# FlightController.net
KiCad netlist of a schematic drawn in Altium Designer
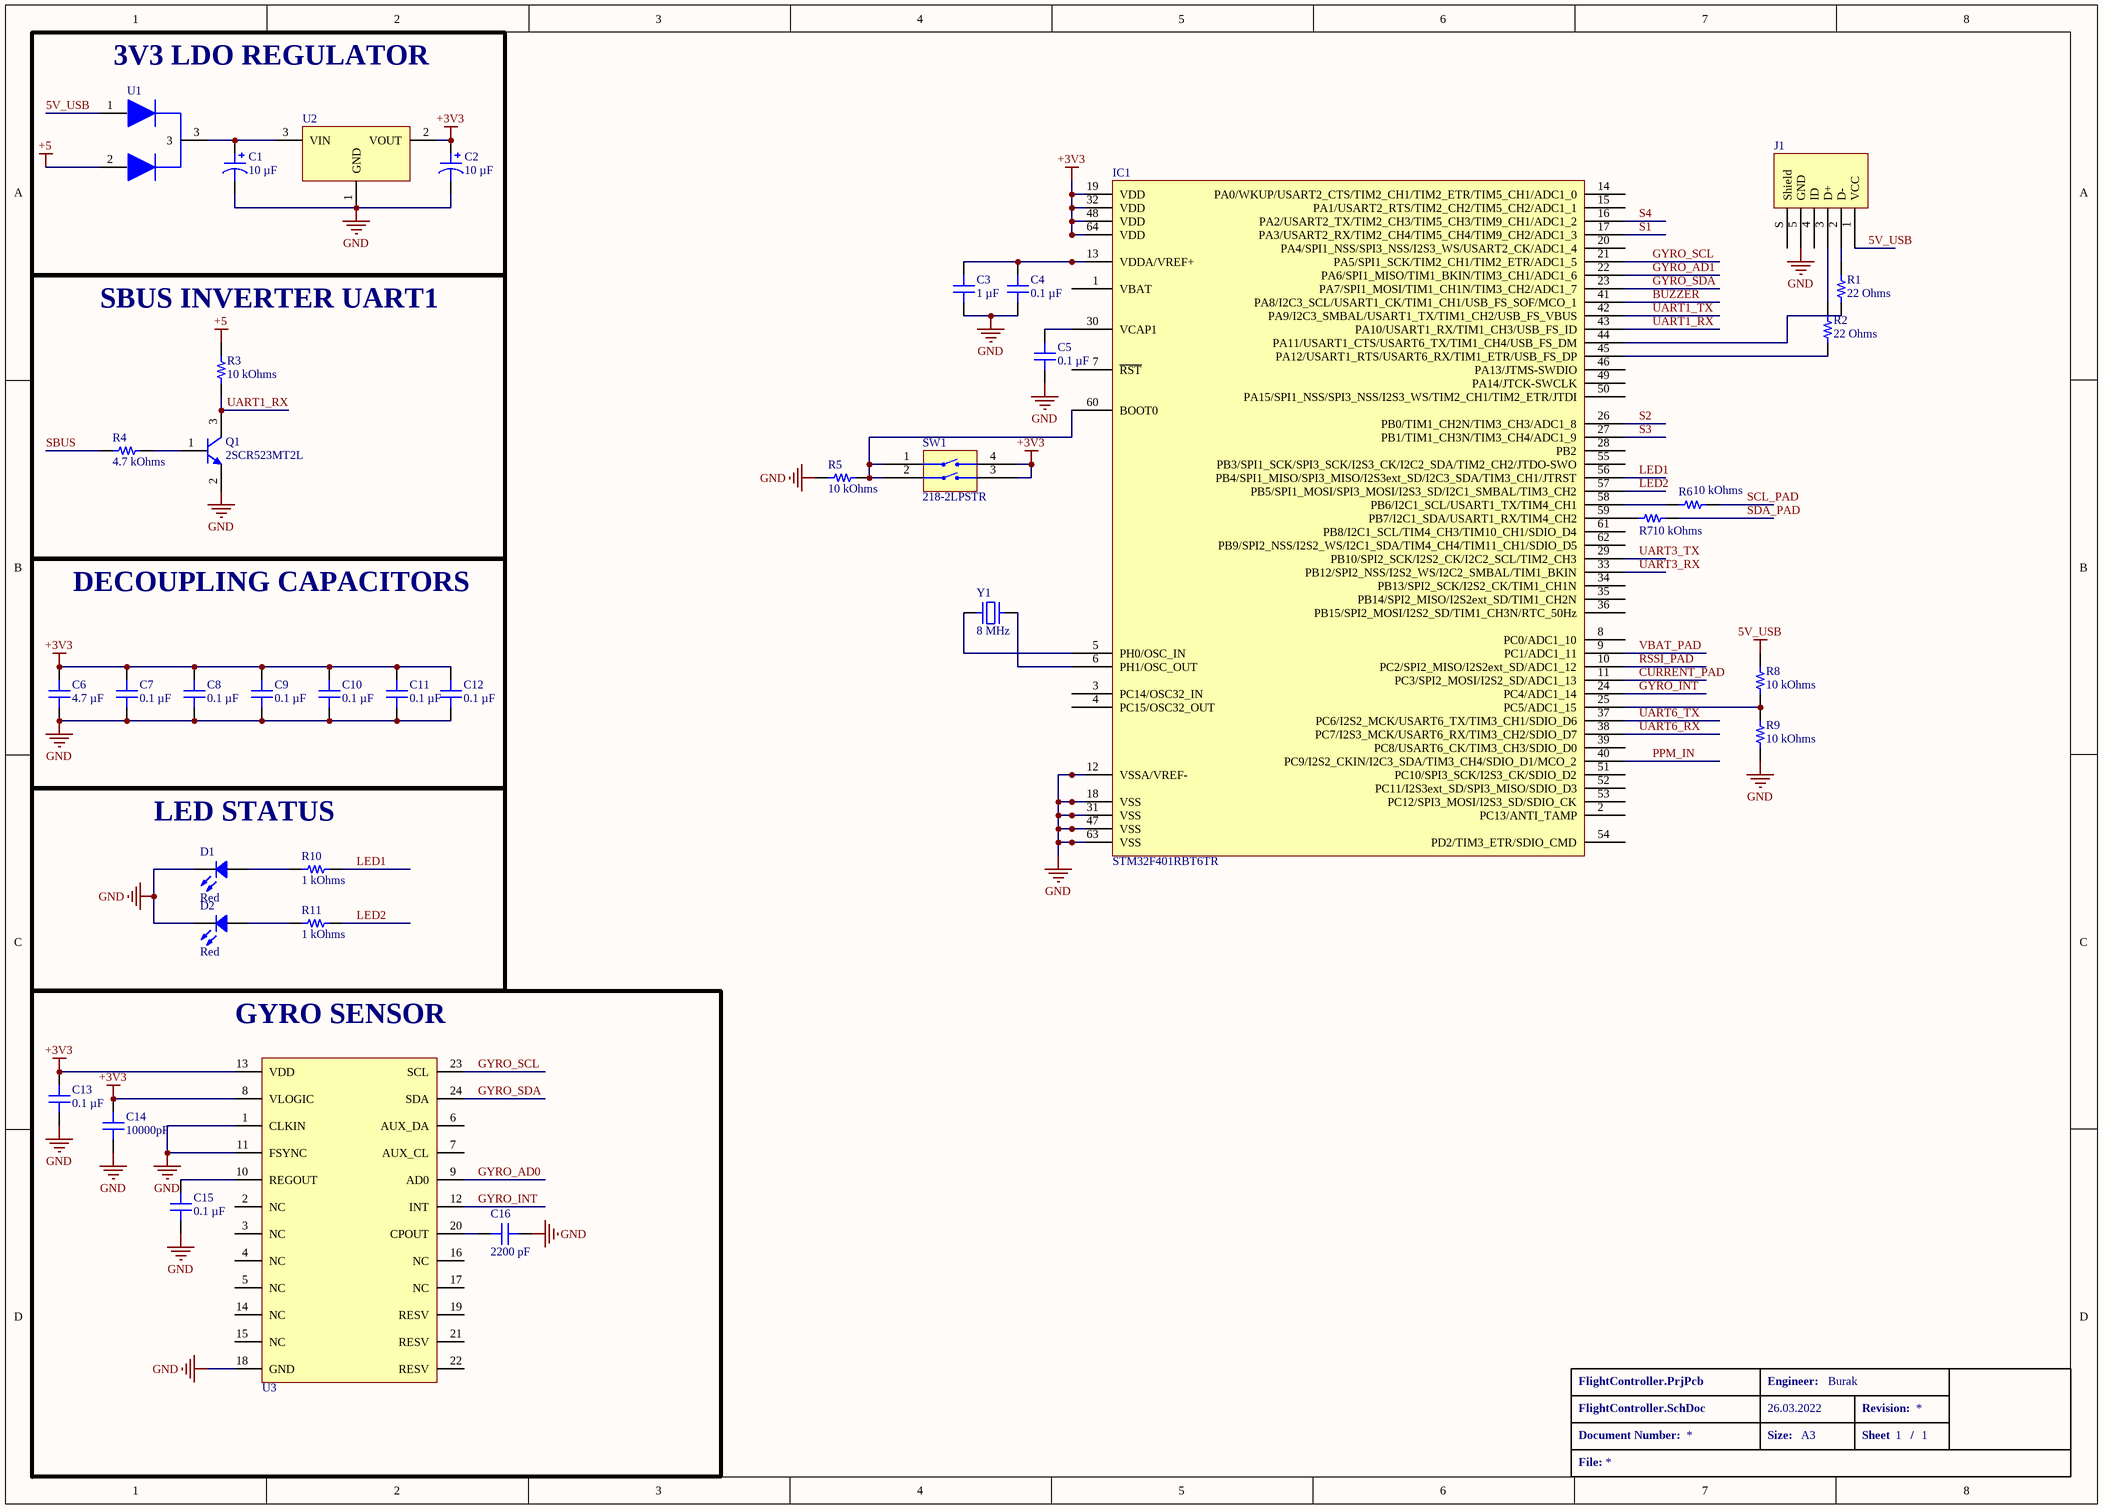
[diagram p0: FlightController.SchDoc]

(export (version "E")
  (design (tool "Eeschema 10.0.6"))
  (components
    (comp (ref "C1")
      (value "10 µF")
      (footprint "CAP ALSMD POLY 5.3MM H5.8MM")
      (description "CAP ALUM POLY 10UF 20% 16V SMD")
      (fields (field (name "PART NUMBER") "875105359001") (field (name "MANUFACTURER") "Würth Elektronik"))
      (libsource (lib "Celestial Altium Library - altium_library") (part "Polarised Capacitor"))
    )
    (comp (ref "C2")
      (value "10 µF")
      (footprint "CAP ALSMD POLY 5.3MM H5.8MM")
      (description "CAP ALUM POLY 10UF 20% 16V SMD")
      (fields (field (name "PART NUMBER") "875105359001") (field (name "MANUFACTURER") "Würth Elektronik"))
      (libsource (lib "Celestial Altium Library - altium_library") (part "Polarised Capacitor"))
    )
    (comp (ref "C3")
      (value "1 µF")
      (footprint "CAP 0805_2012")
      (description "CAP CER 1UF 16V X8R 0805")
      (fields
        (field (name "PART NUMBER") "C2012X8R1C105K125AB")
        (field (name "MANUFACTURER") "TDK Corporation")
      )
      (libsource (lib "Celestial Altium Library - altium_library") (part "Capacitor"))
    )
    (comp (ref "C4")
      (value "0.1 µF")
      (footprint "CAP 0805_2012")
      (description "CAP CER 0.1UF 16V X7R 0805")
      (fields
        (field (name "PART NUMBER") "160R15W104KV4T")
        (field (name "MANUFACTURER") "Johanson Dielectrics Inc.")
      )
      (libsource (lib "Celestial Altium Library - altium_library") (part "Capacitor"))
    )
    (comp (ref "C5")
      (value "0.1 µF")
      (footprint "CAP 0805_2012")
      (description "CAP CER 0.1UF 16V X7R 0805")
      (fields
        (field (name "PART NUMBER") "160R15W104KV4T")
        (field (name "MANUFACTURER") "Johanson Dielectrics Inc.")
      )
      (libsource (lib "Celestial Altium Library - altium_library") (part "Capacitor"))
    )
    (comp (ref "C6")
      (value "4.7 µF")
      (footprint "CAP 0805_2012")
      (description "CAP CER 4.7UF 10V X5R 0805")
      (fields
        (field (name "PART NUMBER") "CL21A475KPFNNNE")
        (field (name "MANUFACTURER") "Samsung Electro-Mechanics")
      )
      (libsource (lib "Celestial Altium Library - altium_library") (part "Capacitor"))
    )
    (comp (ref "C7")
      (value "0.1 µF")
      (footprint "CAP 0805_2012")
      (description "CAP CER 0.1UF 16V X7R 0805")
      (fields
        (field (name "PART NUMBER") "160R15W104KV4T")
        (field (name "MANUFACTURER") "Johanson Dielectrics Inc.")
      )
      (libsource (lib "Celestial Altium Library - altium_library") (part "Capacitor"))
    )
    (comp (ref "C8")
      (value "0.1 µF")
      (footprint "CAP 0805_2012")
      (description "CAP CER 0.1UF 16V X7R 0805")
      (fields
        (field (name "PART NUMBER") "160R15W104KV4T")
        (field (name "MANUFACTURER") "Johanson Dielectrics Inc.")
      )
      (libsource (lib "Celestial Altium Library - altium_library") (part "Capacitor"))
    )
    (comp (ref "C9")
      (value "0.1 µF")
      (footprint "CAP 0805_2012")
      (description "CAP CER 0.1UF 16V X7R 0805")
      (fields
        (field (name "PART NUMBER") "160R15W104KV4T")
        (field (name "MANUFACTURER") "Johanson Dielectrics Inc.")
      )
      (libsource (lib "Celestial Altium Library - altium_library") (part "Capacitor"))
    )
    (comp (ref "C10")
      (value "0.1 µF")
      (footprint "CAP 0805_2012")
      (description "CAP CER 0.1UF 16V X7R 0805")
      (fields
        (field (name "PART NUMBER") "160R15W104KV4T")
        (field (name "MANUFACTURER") "Johanson Dielectrics Inc.")
      )
      (libsource (lib "Celestial Altium Library - altium_library") (part "Capacitor"))
    )
    (comp (ref "C11")
      (value "0.1 µF")
      (footprint "CAP 0805_2012")
      (description "CAP CER 0.1UF 16V X7R 0805")
      (fields
        (field (name "PART NUMBER") "160R15W104KV4T")
        (field (name "MANUFACTURER") "Johanson Dielectrics Inc.")
      )
      (libsource (lib "Celestial Altium Library - altium_library") (part "Capacitor"))
    )
    (comp (ref "C12")
      (value "0.1 µF")
      (footprint "CAP 0805_2012")
      (description "CAP CER 0.1UF 16V X7R 0805")
      (fields
        (field (name "PART NUMBER") "160R15W104KV4T")
        (field (name "MANUFACTURER") "Johanson Dielectrics Inc.")
      )
      (libsource (lib "Celestial Altium Library - altium_library") (part "Capacitor"))
    )
    (comp (ref "C13")
      (value "0.1 µF")
      (footprint "CAP 0805_2012")
      (description "CAP CER 0.1UF 16V X7R 0805")
      (fields
        (field (name "PART NUMBER") "0805B104K160CT")
        (field (name "MANUFACTURER") "Walsin Technology Corporation")
      )
      (libsource (lib "Celestial Altium Library - altium_library") (part "Capacitor"))
    )
    (comp (ref "C14")
      (value "10000pF")
      (footprint "CAP 0805_2012")
      (description "CAP CER 10000PF 16V X7R 0805")
      (fields (field (name "PART NUMBER") "0805YC103KAT2A") (field (name "MANUFACTURER") "AVX Corporation"))
      (libsource (lib "Celestial Altium Library - altium_library") (part "Capacitor"))
    )
    (comp (ref "C15")
      (value "0.1 µF")
      (footprint "CAP 0805_2012")
      (description "CAP CER 0.1UF 16V X7R 0805")
      (fields
        (field (name "PART NUMBER") "0805B104K160CT")
        (field (name "MANUFACTURER") "Walsin Technology Corporation")
      )
      (libsource (lib "Celestial Altium Library - altium_library") (part "Capacitor"))
    )
    (comp (ref "C16")
      (value "2200 pF")
      (footprint "CAP 0805_2012")
      (description "CAP CER 2200PF 10V X7R 0805")
      (fields (field (name "PART NUMBER") "885012207009") (field (name "MANUFACTURER") "Würth Elektronik"))
      (libsource (lib "Celestial Altium Library - altium_library") (part "Capacitor"))
    )
    (comp (ref "D1")
      (value "Red")
      (footprint "LED 1206_3216 RED")
      (description "LED RED CLEAR 1206 SMD")
      (fields (field (name "PART NUMBER") "5973111402F") (field (name "MANUFACTURER") "Dialight"))
      (libsource (lib "Celestial Altium Library - altium_library") (part "LED"))
    )
    (comp (ref "D2")
      (value "Red")
      (footprint "LED 1206_3216 RED")
      (description "LED RED CLEAR 1206 SMD")
      (fields (field (name "PART NUMBER") "5973111402F") (field (name "MANUFACTURER") "Dialight"))
      (libsource (lib "Celestial Altium Library - altium_library") (part "LED"))
    )
    (comp (ref "IC1")
      (value "STM32F401RBT6TR")
      (footprint "ST LQFP-64 10X10MM")
      (description "IC MCU 32BIT 128KB FLASH 64LQFP")
      (fields (field (name "MANUFACTURER") "STMicroelectronics"))
      (libsource (lib "Celestial Altium Library - altium_library") (part "ST STM32F401 64PIN"))
    )
    (comp (ref "J1")
      (value "10118193-0001LF")
      (footprint "FCI USB 10118193-0001LF")
      (description "CONN RCPT USB2.0 MICRO B SMD R/A")
      (fields (field (name "MANUFACTURER") "Amphenol ICC (FCI)"))
      (libsource (lib "Celestial Altium Library - altium_library") (part "USB 2.0 Type B Micro"))
    )
    (comp (ref "Q1")
      (value "2SCR523MT2L")
      (footprint "ROHM SOT-723")
      (description "TRANS NPN 50V 0.1A VMT3")
      (fields (field (name "MANUFACTURER") "Rohm Semiconductor"))
      (libsource (lib "Celestial Altium Library - altium_library") (part "ROHM NPN SOT723 BEC"))
    )
    (comp (ref "R1")
      (value "22 Ohms")
      (footprint "RES 0805_2012")
      (description "RES SMD 22 OHM 0.1% 1/10W 0805")
      (fields
        (field (name "PART NUMBER") "CPF0805B22RE1")
        (field (name "MANUFACTURER") "TE Connectivity Passive Product")
      )
      (libsource (lib "Celestial Altium Library - altium_library") (part "Resistor"))
    )
    (comp (ref "R2")
      (value "22 Ohms")
      (footprint "RES 0805_2012")
      (description "RES SMD 22 OHM 0.1% 1/10W 0805")
      (fields
        (field (name "PART NUMBER") "CPF0805B22RE1")
        (field (name "MANUFACTURER") "TE Connectivity Passive Product")
      )
      (libsource (lib "Celestial Altium Library - altium_library") (part "Resistor"))
    )
    (comp (ref "R3")
      (value "10 kOhms")
      (footprint "RES 0805_2012")
      (description "RES 10K OHM 0.1% 1/10W 0805")
      (fields
        (field (name "PART NUMBER") "RNCS0805BKE10K0")
        (field (name "MANUFACTURER") "Stackpole Electronics Inc")
      )
      (libsource (lib "Celestial Altium Library - altium_library") (part "Resistor"))
    )
    (comp (ref "R4")
      (value "4.7 kOhms")
      (footprint "RES 0805_2012")
      (description "RES SMD 4.7K OHM 5% 0.4W 0805")
      (fields (field (name "PART NUMBER") "RCS08054K70JNEA") (field (name "MANUFACTURER") "Vishay Dale"))
      (libsource (lib "Celestial Altium Library - altium_library") (part "Resistor"))
    )
    (comp (ref "R5")
      (value "10 kOhms")
      (footprint "RES 0805_2012")
      (description "RES 10K OHM 0.1% 1/10W 0805")
      (fields
        (field (name "PART NUMBER") "RNCS0805BKE10K0")
        (field (name "MANUFACTURER") "Stackpole Electronics Inc")
      )
      (libsource (lib "Celestial Altium Library - altium_library") (part "Resistor"))
    )
    (comp (ref "R6")
      (value "10 kOhms")
      (footprint "RES 0805_2012")
      (description "RES 10K OHM 0.1% 1/10W 0805")
      (fields
        (field (name "PART NUMBER") "RNCS0805BKE10K0")
        (field (name "MANUFACTURER") "Stackpole Electronics Inc")
      )
      (libsource (lib "Celestial Altium Library - altium_library") (part "Resistor"))
    )
    (comp (ref "R7")
      (value "10 kOhms")
      (footprint "RES 0805_2012")
      (description "RES 10K OHM 0.1% 1/10W 0805")
      (fields
        (field (name "PART NUMBER") "RNCS0805BKE10K0")
        (field (name "MANUFACTURER") "Stackpole Electronics Inc")
      )
      (libsource (lib "Celestial Altium Library - altium_library") (part "Resistor"))
    )
    (comp (ref "R8")
      (value "10 kOhms")
      (footprint "RES 0805_2012")
      (description "RES 10K OHM 0.1% 1/10W 0805")
      (fields
        (field (name "PART NUMBER") "RNCS0805BKE10K0")
        (field (name "MANUFACTURER") "Stackpole Electronics Inc")
      )
      (libsource (lib "Celestial Altium Library - altium_library") (part "Resistor"))
    )
    (comp (ref "R9")
      (value "10 kOhms")
      (footprint "RES 0805_2012")
      (description "RES 10K OHM 0.1% 1/10W 0805")
      (fields
        (field (name "PART NUMBER") "RNCS0805BKE10K0")
        (field (name "MANUFACTURER") "Stackpole Electronics Inc")
      )
      (libsource (lib "Celestial Altium Library - altium_library") (part "Resistor"))
    )
    (comp (ref "R10")
      (value "1 kOhms")
      (footprint "RES 0805_2012")
      (description "RES 1K OHM 0.1% 1/10W 0805")
      (fields
        (field (name "PART NUMBER") "RNCS0805BKE1K00")
        (field (name "MANUFACTURER") "Stackpole Electronics Inc")
      )
      (libsource (lib "Celestial Altium Library - altium_library") (part "Resistor"))
    )
    (comp (ref "R11")
      (value "1 kOhms")
      (footprint "RES 0805_2012")
      (description "RES 1K OHM 0.1% 1/10W 0805")
      (fields
        (field (name "PART NUMBER") "RNCS0805BKE1K00")
        (field (name "MANUFACTURER") "Stackpole Electronics Inc")
      )
      (libsource (lib "Celestial Altium Library - altium_library") (part "Resistor"))
    )
    (comp (ref "SW1")
      (value "218-2LPSTR")
      (footprint "CTS 218-2LPJ")
      (description "SWITCH SLIDE DIP SPST 25MA 24V")
      (fields (field (name "MANUFACTURER") "CTS Electrocomponents"))
      (libsource (lib "Celestial Altium Library - altium_library") (part "DIP SW 2P"))
    )
    (comp (ref "U1")
      (value "BAT54C")
      (footprint "SOT-23")
      (description "Rectifier Diode Small Signal Schottky 30V 0.2A 5ns Automotive 3-Pin SOT-23 T/R")
      (fields
        (field (name "MANUFACTURER") "NXP Semiconductors")
        (field (name "VOLTAGE") "30V")
        (field (name "DESIGNED BY") "Burak")
      )
      (libsource (lib "UDEMY_Library") (part "BAT54C"))
    )
    (comp (ref "U2")
      (value "IC REG LDO 3.3V 1A SOT223")
      (footprint "SOT223")
      (fields
        (field (name "MANUFACTURER") "ON Semiconductor")
        (field (name "MANUFACTURER PART NUMBER") "NCP1117ST33T3G")
        (field (name "DESIGNED BY") "Burak")
      )
      (libsource (lib "UDEMY_Library") (part "NCP1117ST33T3G"))
    )
    (comp (ref "U3")
      (value "GYRO SENSOR")
      (footprint "QFN_24PINS")
      (description "IMU ACCEL/GYRO 3-AXIS I2C 24QFN")
      (fields
        (field (name "MANUFACTURER") "TDK InvenSense")
        (field (name "MANUFACTURER PART NUMBER") "MPU-6050")
        (field (name "DESIGNED BY") "Burak")
      )
      (libsource (lib "UDEMY_Library") (part "MPU-6050"))
    )
    (comp (ref "Y1")
      (value "8 MHz")
      (footprint "ABRACON ABLS")
      (description "CRYSTAL 8.0000MHZ 18PF SMD")
      (fields (field (name "PART NUMBER") "ABLS-8.000MHZ-SD7Y-T") (field (name "MANUFACTURER") "Abracon LLC"))
      (libsource (lib "Celestial Altium Library - altium_library") (part "Abracon Crystal ABLS"))
    )
  )
  (nets
    (net (code "1") (name "+3V3") (class "Default")
      (node (ref "C10") (pin "2") (pinfunction "2_2") (pintype "passive"))
      (node (ref "C11") (pin "2") (pinfunction "2_2") (pintype "passive"))
      (node (ref "C12") (pin "2") (pinfunction "2_2") (pintype "passive"))
      (node (ref "C13") (pin "2") (pinfunction "2_2") (pintype "passive"))
      (node (ref "C14") (pin "2") (pinfunction "2_2") (pintype "passive"))
      (node (ref "C2") (pin "1") (pinfunction "1_1") (pintype "passive"))
      (node (ref "C6") (pin "2") (pinfunction "2_2") (pintype "passive"))
      (node (ref "C7") (pin "2") (pinfunction "2_2") (pintype "passive"))
      (node (ref "C8") (pin "2") (pinfunction "2_2") (pintype "passive"))
      (node (ref "C9") (pin "2") (pinfunction "2_2") (pintype "passive"))
      (node (ref "IC1") (pin "19") (pinfunction "VDD_19") (pintype "passive"))
      (node (ref "IC1") (pin "32") (pinfunction "VDD_32") (pintype "passive"))
      (node (ref "IC1") (pin "48") (pinfunction "VDD_48") (pintype "passive"))
      (node (ref "IC1") (pin "64") (pinfunction "VDD_64") (pintype "passive"))
      (node (ref "SW1") (pin "3") (pinfunction "GND_3") (pintype "passive"))
      (node (ref "SW1") (pin "4") (pinfunction "GND_4") (pintype "passive"))
      (node (ref "U2") (pin "2") (pinfunction "VOUT_2") (pintype "passive"))
      (node (ref "U3") (pin "13") (pinfunction "VDD_13") (pintype "passive"))
      (node (ref "U3") (pin "8") (pinfunction "VLOGIC_8") (pintype "passive"))
    )
    (net (code "2") (name "+5") (class "Default")
      (node (ref "R3") (pin "2") (pinfunction "2_2") (pintype "passive"))
      (node (ref "U1") (pin "2") (pinfunction "2_2") (pintype "passive"))
    )
    (net (code "3") (name "/BUZZER") (class "Default")
      (node (ref "IC1") (pin "41") (pinfunction "PA8/I2C3_SCL/USART1_CK/TIM1_CH1/USB_FS_SOF/MCO_1_41") (pintype "passive"))
    )
    (net (code "4") (name "/CURRENT_PAD") (class "Default")
      (node (ref "IC1") (pin "11") (pinfunction "PC3/SPI2_MOSI/I2S2_SD/ADC1_13_11") (pintype "passive"))
    )
    (net (code "5") (name "/GYRO_AD0") (class "Default")
      (node (ref "U3") (pin "9") (pinfunction "AD0_9") (pintype "passive"))
    )
    (net (code "6") (name "/GYRO_AD1") (class "Default")
      (node (ref "IC1") (pin "22") (pinfunction "PA6/SPI1_MISO/TIM1_BKIN/TIM3_CH1/ADC1_6_22") (pintype "passive"))
    )
    (net (code "7") (name "/GYRO_INT") (class "Default")
      (node (ref "IC1") (pin "24") (pinfunction "PC4/ADC1_14_24") (pintype "passive"))
      (node (ref "U3") (pin "12") (pinfunction "INT_12") (pintype "passive"))
    )
    (net (code "8") (name "/GYRO_SCL") (class "Default")
      (node (ref "IC1") (pin "21") (pinfunction "PA5/SPI1_SCK/TIM2_CH1/TIM2_ETR/ADC1_5_21") (pintype "passive"))
      (node (ref "U3") (pin "23") (pinfunction "SCL_23") (pintype "passive"))
    )
    (net (code "9") (name "/GYRO_SDA") (class "Default")
      (node (ref "IC1") (pin "23") (pinfunction "PA7/SPI1_MOSI/TIM1_CH1N/TIM3_CH2/ADC1_7_23") (pintype "passive"))
      (node (ref "U3") (pin "24") (pinfunction "SDA_24") (pintype "passive"))
    )
    (net (code "10") (name "/LED1") (class "Default")
      (node (ref "IC1") (pin "56") (pinfunction "PB4/SPI1_MISO/SPI3_MISO/I2S3ext_SD/I2C3_SDA/TIM3_CH1/JTRST_56") (pintype "passive"))
      (node (ref "R10") (pin "2") (pinfunction "2_2") (pintype "passive"))
    )
    (net (code "11") (name "/LED2") (class "Default")
      (node (ref "IC1") (pin "57") (pinfunction "PB5/SPI1_MOSI/SPI3_MOSI/I2S3_SD/I2C1_SMBAL/TIM3_CH2_57") (pintype "passive"))
      (node (ref "R11") (pin "2") (pinfunction "2_2") (pintype "passive"))
    )
    (net (code "12") (name "/PPM_IN") (class "Default")
      (node (ref "IC1") (pin "40") (pinfunction "PC9/I2S2_CKIN/I2C3_SDA/TIM3_CH4/SDIO_D1/MCO_2_40") (pintype "passive"))
    )
    (net (code "13") (name "/RSSI_PAD") (class "Default")
      (node (ref "IC1") (pin "10") (pinfunction "PC2/SPI2_MISO/I2S2ext_SD/ADC1_12_10") (pintype "passive"))
    )
    (net (code "14") (name "/S1") (class "Default")
      (node (ref "IC1") (pin "17") (pinfunction "PA3/USART2_RX/TIM2_CH4/TIM5_CH4/TIM9_CH2/ADC1_3_17") (pintype "passive"))
    )
    (net (code "15") (name "/S2") (class "Default")
      (node (ref "IC1") (pin "26") (pinfunction "PB0/TIM1_CH2N/TIM3_CH3/ADC1_8_26") (pintype "passive"))
    )
    (net (code "16") (name "/S3") (class "Default")
      (node (ref "IC1") (pin "27") (pinfunction "PB1/TIM1_CH3N/TIM3_CH4/ADC1_9_27") (pintype "passive"))
    )
    (net (code "17") (name "/S4") (class "Default")
      (node (ref "IC1") (pin "16") (pinfunction "PA2/USART2_TX/TIM2_CH3/TIM5_CH3/TIM9_CH1/ADC1_2_16") (pintype "passive"))
    )
    (net (code "18") (name "/SBUS") (class "Default")
      (node (ref "R4") (pin "1") (pinfunction "1_1") (pintype "passive"))
    )
    (net (code "19") (name "/SCL_PAD") (class "Default")
      (node (ref "R6") (pin "1") (pinfunction "1_1") (pintype "passive"))
    )
    (net (code "20") (name "/SDA_PAD") (class "Default")
      (node (ref "R7") (pin "1") (pinfunction "1_1") (pintype "passive"))
    )
    (net (code "21") (name "/UART1_RX") (class "Default")
      (node (ref "IC1") (pin "43") (pinfunction "PA10/USART1_RX/TIM1_CH3/USB_FS_ID_43") (pintype "passive"))
      (node (ref "Q1") (pin "3") (pinfunction "C_3") (pintype "passive"))
      (node (ref "R3") (pin "1") (pinfunction "1_1") (pintype "passive"))
    )
    (net (code "22") (name "/UART1_TX") (class "Default")
      (node (ref "IC1") (pin "42") (pinfunction "PA9/I2C3_SMBAL/USART1_TX/TIM1_CH2/USB_FS_VBUS_42") (pintype "passive"))
    )
    (net (code "23") (name "/UART3_RX") (class "Default")
      (node (ref "IC1") (pin "33") (pinfunction "PB12/SPI2_NSS/I2S2_WS/I2C2_SMBAL/TIM1_BKIN_33") (pintype "passive"))
    )
    (net (code "24") (name "/UART3_TX") (class "Default")
      (node (ref "IC1") (pin "29") (pinfunction "PB10/SPI2_SCK/I2S2_CK/I2C2_SCL/TIM2_CH3_29") (pintype "passive"))
    )
    (net (code "25") (name "/UART6_RX") (class "Default")
      (node (ref "IC1") (pin "38") (pinfunction "PC7/I2S3_MCK/USART6_RX/TIM3_CH2/SDIO_D7_38") (pintype "passive"))
    )
    (net (code "26") (name "/UART6_TX") (class "Default")
      (node (ref "IC1") (pin "37") (pinfunction "PC6/I2S2_MCK/USART6_TX/TIM3_CH1/SDIO_D6_37") (pintype "passive"))
    )
    (net (code "27") (name "/VBAT_PAD") (class "Default")
      (node (ref "IC1") (pin "9") (pinfunction "PC1/ADC1_11_9") (pintype "passive"))
    )
    (net (code "28") (name "5V_USB") (class "Default")
      (node (ref "J1") (pin "1") (pinfunction "VCC_1") (pintype "passive"))
      (node (ref "R8") (pin "2") (pinfunction "2_2") (pintype "passive"))
      (node (ref "U1") (pin "1") (pinfunction "1_1") (pintype "passive"))
    )
    (net (code "29") (name "GND") (class "Default")
      (node (ref "C1") (pin "2") (pinfunction "2_2") (pintype "passive"))
      (node (ref "C10") (pin "1") (pinfunction "1_1") (pintype "passive"))
      (node (ref "C11") (pin "1") (pinfunction "1_1") (pintype "passive"))
      (node (ref "C12") (pin "1") (pinfunction "1_1") (pintype "passive"))
      (node (ref "C13") (pin "1") (pinfunction "1_1") (pintype "passive"))
      (node (ref "C14") (pin "1") (pinfunction "1_1") (pintype "passive"))
      (node (ref "C15") (pin "1") (pinfunction "1_1") (pintype "passive"))
      (node (ref "C16") (pin "2") (pinfunction "2_2") (pintype "passive"))
      (node (ref "C2") (pin "2") (pinfunction "2_2") (pintype "passive"))
      (node (ref "C3") (pin "1") (pinfunction "1_1") (pintype "passive"))
      (node (ref "C4") (pin "1") (pinfunction "1_1") (pintype "passive"))
      (node (ref "C5") (pin "1") (pinfunction "1_1") (pintype "passive"))
      (node (ref "C6") (pin "1") (pinfunction "1_1") (pintype "passive"))
      (node (ref "C7") (pin "1") (pinfunction "1_1") (pintype "passive"))
      (node (ref "C8") (pin "1") (pinfunction "1_1") (pintype "passive"))
      (node (ref "C9") (pin "1") (pinfunction "1_1") (pintype "passive"))
      (node (ref "D1") (pin "2") (pinfunction "2_2") (pintype "passive"))
      (node (ref "D2") (pin "2") (pinfunction "2_2") (pintype "passive"))
      (node (ref "IC1") (pin "12") (pinfunction "VSSA/VREF-_12") (pintype "passive"))
      (node (ref "IC1") (pin "18") (pinfunction "VSS_18") (pintype "passive"))
      (node (ref "IC1") (pin "31") (pinfunction "VSS_31") (pintype "passive"))
      (node (ref "IC1") (pin "47") (pinfunction "VSS_47") (pintype "passive"))
      (node (ref "IC1") (pin "63") (pinfunction "VSS_63") (pintype "passive"))
      (node (ref "J1") (pin "5") (pinfunction "GND_5") (pintype "passive"))
      (node (ref "Q1") (pin "2") (pinfunction "E_2") (pintype "passive"))
      (node (ref "R5") (pin "2") (pinfunction "2_2") (pintype "passive"))
      (node (ref "R9") (pin "1") (pinfunction "1_1") (pintype "passive"))
      (node (ref "U2") (pin "1") (pinfunction "GND_1") (pintype "passive"))
      (node (ref "U3") (pin "1") (pinfunction "CLKIN_1") (pintype "passive"))
      (node (ref "U3") (pin "11") (pinfunction "FSYNC_11") (pintype "passive"))
      (node (ref "U3") (pin "18") (pinfunction "GND_18") (pintype "passive"))
    )
    (net (code "30") (name "Net-(D1-Pad1)") (class "Default")
      (node (ref "D1") (pin "1") (pinfunction "1_1") (pintype "passive"))
      (node (ref "R10") (pin "1") (pinfunction "1_1") (pintype "passive"))
    )
    (net (code "31") (name "Net-(D2-Pad1)") (class "Default")
      (node (ref "D2") (pin "1") (pinfunction "1_1") (pintype "passive"))
      (node (ref "R11") (pin "1") (pinfunction "1_1") (pintype "passive"))
    )
    (net (code "32") (name "Net-(IC1-BOOT0)") (class "Default")
      (node (ref "IC1") (pin "60") (pinfunction "BOOT0_60") (pintype "passive"))
      (node (ref "R5") (pin "1") (pinfunction "1_1") (pintype "passive"))
      (node (ref "SW1") (pin "1") (pinfunction "GND_1") (pintype "passive"))
      (node (ref "SW1") (pin "2") (pinfunction "GND_2") (pintype "passive"))
    )
    (net (code "33") (name "Net-(IC1-PA11{slash}USART1_CTS{slash}USART6_TX{slash}TIM1_CH4{slash}USB_FS_DM)") (class "Default")
      (node (ref "IC1") (pin "44") (pinfunction "PA11/USART1_CTS/USART6_TX/TIM1_CH4/USB_FS_DM_44") (pintype "passive"))
      (node (ref "R1") (pin "1") (pinfunction "1_1") (pintype "passive"))
    )
    (net (code "34") (name "Net-(IC1-PA12{slash}USART1_RTS{slash}USART6_RX{slash}TIM1_ETR{slash}USB_FS_DP)") (class "Default")
      (node (ref "IC1") (pin "45") (pinfunction "PA12/USART1_RTS/USART6_RX/TIM1_ETR/USB_FS_DP_45") (pintype "passive"))
      (node (ref "R2") (pin "1") (pinfunction "1_1") (pintype "passive"))
    )
    (net (code "35") (name "Net-(IC1-PB6{slash}I2C1_SCL{slash}USART1_TX{slash}TIM4_CH1)") (class "Default")
      (node (ref "IC1") (pin "58") (pinfunction "PB6/I2C1_SCL/USART1_TX/TIM4_CH1_58") (pintype "passive"))
      (node (ref "R6") (pin "2") (pinfunction "2_2") (pintype "passive"))
    )
    (net (code "36") (name "Net-(IC1-PB7{slash}I2C1_SDA{slash}USART1_RX{slash}TIM4_CH2)") (class "Default")
      (node (ref "IC1") (pin "59") (pinfunction "PB7/I2C1_SDA/USART1_RX/TIM4_CH2_59") (pintype "passive"))
      (node (ref "R7") (pin "2") (pinfunction "2_2") (pintype "passive"))
    )
    (net (code "37") (name "Net-(IC1-PC5{slash}ADC1_15)") (class "Default")
      (node (ref "IC1") (pin "25") (pinfunction "PC5/ADC1_15_25") (pintype "passive"))
      (node (ref "R8") (pin "1") (pinfunction "1_1") (pintype "passive"))
      (node (ref "R9") (pin "2") (pinfunction "2_2") (pintype "passive"))
    )
    (net (code "38") (name "Net-(IC1-PH0{slash}OSC_IN)") (class "Default")
      (node (ref "IC1") (pin "5") (pinfunction "PH0/OSC_IN_5") (pintype "passive"))
      (node (ref "Y1") (pin "1") (pinfunction "1_1") (pintype "passive"))
    )
    (net (code "39") (name "Net-(IC1-PH1{slash}OSC_OUT)") (class "Default")
      (node (ref "IC1") (pin "6") (pinfunction "PH1/OSC_OUT_6") (pintype "passive"))
      (node (ref "Y1") (pin "2") (pinfunction "2_2") (pintype "passive"))
    )
    (net (code "40") (name "Net-(IC1-VCAP1)") (class "Default")
      (node (ref "C5") (pin "2") (pinfunction "2_2") (pintype "passive"))
      (node (ref "IC1") (pin "30") (pinfunction "VCAP1_30") (pintype "passive"))
    )
    (net (code "41") (name "Net-(IC1-VDDA{slash}VREF+)") (class "Default")
      (node (ref "C3") (pin "2") (pinfunction "2_2") (pintype "passive"))
      (node (ref "C4") (pin "2") (pinfunction "2_2") (pintype "passive"))
      (node (ref "IC1") (pin "13") (pinfunction "VDDA/VREF+_13") (pintype "passive"))
    )
    (net (code "42") (name "Net-(J1-D+)") (class "Default")
      (node (ref "J1") (pin "3") (pinfunction "D+_3") (pintype "passive"))
      (node (ref "R2") (pin "2") (pinfunction "2_2") (pintype "passive"))
    )
    (net (code "43") (name "Net-(J1-D-)") (class "Default")
      (node (ref "J1") (pin "2") (pinfunction "D-_2") (pintype "passive"))
      (node (ref "R1") (pin "2") (pinfunction "2_2") (pintype "passive"))
    )
    (net (code "44") (name "Net-(Q1-B)") (class "Default")
      (node (ref "Q1") (pin "1") (pinfunction "B_1") (pintype "passive"))
      (node (ref "R4") (pin "2") (pinfunction "2_2") (pintype "passive"))
    )
    (net (code "45") (name "Net-(U2-VIN)") (class "Default")
      (node (ref "C1") (pin "1") (pinfunction "1_1") (pintype "passive"))
      (node (ref "U1") (pin "3") (pinfunction "3_3") (pintype "passive"))
      (node (ref "U2") (pin "3") (pinfunction "VIN_3") (pintype "passive"))
    )
    (net (code "46") (name "Net-(U3-CPOUT)") (class "Default")
      (node (ref "C16") (pin "1") (pinfunction "1_1") (pintype "passive"))
      (node (ref "U3") (pin "20") (pinfunction "CPOUT_20") (pintype "passive"))
    )
    (net (code "47") (name "Net-(U3-REGOUT)") (class "Default")
      (node (ref "C15") (pin "2") (pinfunction "2_2") (pintype "passive"))
      (node (ref "U3") (pin "10") (pinfunction "REGOUT_10") (pintype "passive"))
    )
    (net (code "48") (name "unconnected-(IC1-PA0{slash}WKUP{slash}USART2_CTS{slash}TIM2_CH1{slash}TIM2_ETR{slash}TIM5_CH1{slash}ADC1_0-Pad14)") (class "Default")
      (node (ref "IC1") (pin "14") (pinfunction "PA0/WKUP/USART2_CTS/TIM2_CH1/TIM2_ETR/TIM5_CH1/ADC1_0_14") (pintype "passive"))
    )
    (net (code "49") (name "unconnected-(IC1-PA1{slash}USART2_RTS{slash}TIM2_CH2{slash}TIM5_CH2{slash}ADC1_1-Pad15)") (class "Default")
      (node (ref "IC1") (pin "15") (pinfunction "PA1/USART2_RTS/TIM2_CH2/TIM5_CH2/ADC1_1_15") (pintype "passive"))
    )
    (net (code "50") (name "unconnected-(IC1-PA4{slash}SPI1_NSS{slash}SPI3_NSS{slash}I2S3_WS{slash}USART2_CK{slash}ADC1_4-Pad20)") (class "Default")
      (node (ref "IC1") (pin "20") (pinfunction "PA4/SPI1_NSS/SPI3_NSS/I2S3_WS/USART2_CK/ADC1_4_20") (pintype "passive"))
    )
    (net (code "51") (name "unconnected-(IC1-PA13{slash}JTMS-SWDIO-Pad46)") (class "Default")
      (node (ref "IC1") (pin "46") (pinfunction "PA13/JTMS-SWDIO_46") (pintype "passive"))
    )
    (net (code "52") (name "unconnected-(IC1-PA14{slash}JTCK-SWCLK-Pad49)") (class "Default")
      (node (ref "IC1") (pin "49") (pinfunction "PA14/JTCK-SWCLK_49") (pintype "passive"))
    )
    (net (code "53") (name "unconnected-(IC1-PA15{slash}SPI1_NSS{slash}SPI3_NSS{slash}I2S3_WS{slash}TIM2_CH1{slash}TIM2_ETR{slash}JTDI-Pad50)") (class "Default")
      (node (ref "IC1") (pin "50") (pinfunction "PA15/SPI1_NSS/SPI3_NSS/I2S3_WS/TIM2_CH1/TIM2_ETR/JTDI_50") (pintype "passive"))
    )
    (net (code "54") (name "unconnected-(IC1-PB2-Pad28)") (class "Default")
      (node (ref "IC1") (pin "28") (pinfunction "PB2_28") (pintype "passive"))
    )
    (net (code "55") (name "unconnected-(IC1-PB3{slash}SPI1_SCK{slash}SPI3_SCK{slash}I2S3_CK{slash}I2C2_SDA{slash}TIM2_CH2{slash}JTDO-SWO-Pad55)") (class "Default")
      (node (ref "IC1") (pin "55") (pinfunction "PB3/SPI1_SCK/SPI3_SCK/I2S3_CK/I2C2_SDA/TIM2_CH2/JTDO-SWO_55") (pintype "passive"))
    )
    (net (code "56") (name "unconnected-(IC1-PB8{slash}I2C1_SCL{slash}TIM4_CH3{slash}TIM10_CH1{slash}SDIO_D4-Pad61)") (class "Default")
      (node (ref "IC1") (pin "61") (pinfunction "PB8/I2C1_SCL/TIM4_CH3/TIM10_CH1/SDIO_D4_61") (pintype "passive"))
    )
    (net (code "57") (name "unconnected-(IC1-PB9{slash}SPI2_NSS{slash}I2S2_WS{slash}I2C1_SDA{slash}TIM4_CH4{slash}TIM11_CH1{slash}SDIO_D5-Pad62)") (class "Default")
      (node (ref "IC1") (pin "62") (pinfunction "PB9/SPI2_NSS/I2S2_WS/I2C1_SDA/TIM4_CH4/TIM11_CH1/SDIO_D5_62") (pintype "passive"))
    )
    (net (code "58") (name "unconnected-(IC1-PB13{slash}SPI2_SCK{slash}I2S2_CK{slash}TIM1_CH1N-Pad34)") (class "Default")
      (node (ref "IC1") (pin "34") (pinfunction "PB13/SPI2_SCK/I2S2_CK/TIM1_CH1N_34") (pintype "passive"))
    )
    (net (code "59") (name "unconnected-(IC1-PB14{slash}SPI2_MISO{slash}I2S2ext_SD{slash}TIM1_CH2N-Pad35)") (class "Default")
      (node (ref "IC1") (pin "35") (pinfunction "PB14/SPI2_MISO/I2S2ext_SD/TIM1_CH2N_35") (pintype "passive"))
    )
    (net (code "60") (name "unconnected-(IC1-PB15{slash}SPI2_MOSI{slash}I2S2_SD{slash}TIM1_CH3N{slash}RTC_50Hz-Pad36)") (class "Default")
      (node (ref "IC1") (pin "36") (pinfunction "PB15/SPI2_MOSI/I2S2_SD/TIM1_CH3N/RTC_50Hz_36") (pintype "passive"))
    )
    (net (code "61") (name "unconnected-(IC1-PC0{slash}ADC1_10-Pad8)") (class "Default")
      (node (ref "IC1") (pin "8") (pinfunction "PC0/ADC1_10_8") (pintype "passive"))
    )
    (net (code "62") (name "unconnected-(IC1-PC8{slash}USART6_CK{slash}TIM3_CH3{slash}SDIO_D0-Pad39)") (class "Default")
      (node (ref "IC1") (pin "39") (pinfunction "PC8/USART6_CK/TIM3_CH3/SDIO_D0_39") (pintype "passive"))
    )
    (net (code "63") (name "unconnected-(IC1-PC10{slash}SPI3_SCK{slash}I2S3_CK{slash}SDIO_D2-Pad51)") (class "Default")
      (node (ref "IC1") (pin "51") (pinfunction "PC10/SPI3_SCK/I2S3_CK/SDIO_D2_51") (pintype "passive"))
    )
    (net (code "64") (name "unconnected-(IC1-PC11{slash}I2S3ext_SD{slash}SPI3_MISO{slash}SDIO_D3-Pad52)") (class "Default")
      (node (ref "IC1") (pin "52") (pinfunction "PC11/I2S3ext_SD/SPI3_MISO/SDIO_D3_52") (pintype "passive"))
    )
    (net (code "65") (name "unconnected-(IC1-PC12{slash}SPI3_MOSI{slash}I2S3_SD{slash}SDIO_CK-Pad53)") (class "Default")
      (node (ref "IC1") (pin "53") (pinfunction "PC12/SPI3_MOSI/I2S3_SD/SDIO_CK_53") (pintype "passive"))
    )
    (net (code "66") (name "unconnected-(IC1-PC13{slash}ANTI_TAMP-Pad2)") (class "Default")
      (node (ref "IC1") (pin "2") (pinfunction "PC13/ANTI_TAMP_2") (pintype "passive"))
    )
    (net (code "67") (name "unconnected-(IC1-PC14{slash}OSC32_IN-Pad3)") (class "Default")
      (node (ref "IC1") (pin "3") (pinfunction "PC14/OSC32_IN_3") (pintype "passive"))
    )
    (net (code "68") (name "unconnected-(IC1-PC15{slash}OSC32_OUT-Pad4)") (class "Default")
      (node (ref "IC1") (pin "4") (pinfunction "PC15/OSC32_OUT_4") (pintype "passive"))
    )
    (net (code "69") (name "unconnected-(IC1-PD2{slash}TIM3_ETR{slash}SDIO_CMD-Pad54)") (class "Default")
      (node (ref "IC1") (pin "54") (pinfunction "PD2/TIM3_ETR/SDIO_CMD_54") (pintype "passive"))
    )
    (net (code "70") (name "unconnected-(IC1-VBAT-Pad1)") (class "Default")
      (node (ref "IC1") (pin "1") (pinfunction "VBAT_1") (pintype "passive"))
    )
    (net (code "71") (name "unconnected-(IC1-~{RST}-Pad7)") (class "Default")
      (node (ref "IC1") (pin "7") (pinfunction "~{RST}_7") (pintype "passive"))
    )
    (net (code "72") (name "unconnected-(J1-ID-Pad4)") (class "Default")
      (node (ref "J1") (pin "4") (pinfunction "ID_4") (pintype "passive"))
    )
    (net (code "73") (name "unconnected-(J1-Shield-PadS)") (class "Default")
      (node (ref "J1") (pin "S") (pinfunction "Shield_S") (pintype "passive"))
    )
    (net (code "74") (name "unconnected-(U3-AUX_CL-Pad7)") (class "Default")
      (node (ref "U3") (pin "7") (pinfunction "AUX_CL_7") (pintype "passive"))
    )
    (net (code "75") (name "unconnected-(U3-AUX_DA-Pad6)") (class "Default")
      (node (ref "U3") (pin "6") (pinfunction "AUX_DA_6") (pintype "passive"))
    )
    (net (code "76") (name "unconnected-(U3-NC-Pad2)") (class "Default")
      (node (ref "U3") (pin "2") (pinfunction "NC_2") (pintype "passive"))
    )
    (net (code "77") (name "unconnected-(U3-NC-Pad3)") (class "Default")
      (node (ref "U3") (pin "3") (pinfunction "NC_3") (pintype "passive"))
    )
    (net (code "78") (name "unconnected-(U3-NC-Pad4)") (class "Default")
      (node (ref "U3") (pin "4") (pinfunction "NC_4") (pintype "passive"))
    )
    (net (code "79") (name "unconnected-(U3-NC-Pad5)") (class "Default")
      (node (ref "U3") (pin "5") (pinfunction "NC_5") (pintype "passive"))
    )
    (net (code "80") (name "unconnected-(U3-NC-Pad14)") (class "Default")
      (node (ref "U3") (pin "14") (pinfunction "NC_14") (pintype "passive"))
    )
    (net (code "81") (name "unconnected-(U3-NC-Pad15)") (class "Default")
      (node (ref "U3") (pin "15") (pinfunction "NC_15") (pintype "passive"))
    )
    (net (code "82") (name "unconnected-(U3-NC-Pad16)") (class "Default")
      (node (ref "U3") (pin "16") (pinfunction "NC_16") (pintype "passive"))
    )
    (net (code "83") (name "unconnected-(U3-NC-Pad17)") (class "Default")
      (node (ref "U3") (pin "17") (pinfunction "NC_17") (pintype "passive"))
    )
    (net (code "84") (name "unconnected-(U3-RESV-Pad19)") (class "Default")
      (node (ref "U3") (pin "19") (pinfunction "RESV_19") (pintype "passive"))
    )
    (net (code "85") (name "unconnected-(U3-RESV-Pad21)") (class "Default")
      (node (ref "U3") (pin "21") (pinfunction "RESV_21") (pintype "passive"))
    )
    (net (code "86") (name "unconnected-(U3-RESV-Pad22)") (class "Default")
      (node (ref "U3") (pin "22") (pinfunction "RESV_22") (pintype "passive"))
    )
  )
)
